# Sheet1.net
KiCad netlist of a schematic drawn in Altium Designer
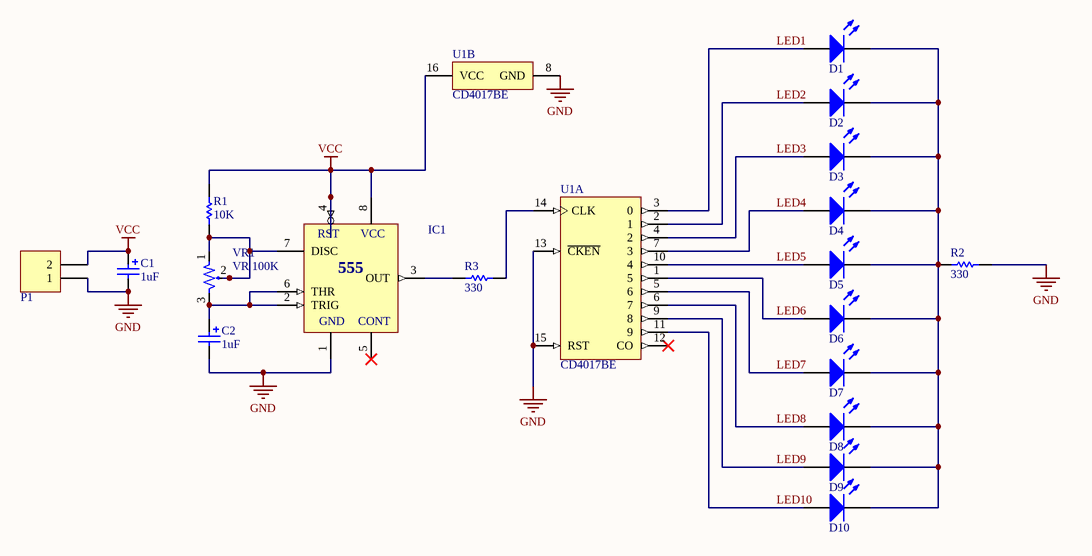
[diagram p0: Sheet1.SchDoc]

(export (version "E")
  (design (tool "Eeschema 10.0.6"))
  (components
    (comp (ref "C1")
      (value "1uF")
      (footprint "CP1/2")
      (description "Polarized Capacitor (Radial)")
      (fields (field (name "Comment") "Cap Pol"))
      (libsource (lib "PIF_Library") (part "Cap Pol"))
    )
    (comp (ref "C2")
      (value "1uF")
      (footprint "CP1/2")
      (description "Polarized Capacitor (Radial)")
      (fields (field (name "Comment") "Cap Pol"))
      (libsource (lib "PIF_Library") (part "Cap Pol"))
    )
    (comp (ref "D1") (value "LED") (footprint "LED-5mm") (libsource (lib "PIF_Library") (part "LED")))
    (comp (ref "D2") (value "LED") (footprint "LED-5mm") (libsource (lib "PIF_Library") (part "LED")))
    (comp (ref "D3") (value "LED") (footprint "LED-5mm") (libsource (lib "PIF_Library") (part "LED")))
    (comp (ref "D4") (value "LED") (footprint "LED-5mm") (libsource (lib "PIF_Library") (part "LED")))
    (comp (ref "D5") (value "LED") (footprint "LED-5mm") (libsource (lib "PIF_Library") (part "LED")))
    (comp (ref "D6") (value "LED") (footprint "LED-5mm") (libsource (lib "PIF_Library") (part "LED")))
    (comp (ref "D7") (value "LED") (footprint "LED-5mm") (libsource (lib "PIF_Library") (part "LED")))
    (comp (ref "D8") (value "LED") (footprint "LED-5mm") (libsource (lib "PIF_Library") (part "LED")))
    (comp (ref "D9") (value "LED") (footprint "LED-5mm") (libsource (lib "PIF_Library") (part "LED")))
    (comp (ref "D10") (value "LED") (footprint "LED-5mm") (libsource (lib "PIF_Library") (part "LED")))
    (comp (ref "IC1")
      (value "LM555")
      (footprint "DIP8/W0.3")
      (description "Timer")
      (libsource (lib "PIF_Library") (part "LM555"))
    )
    (comp (ref "P1")
      (value "Domino 2")
      (footprint "DOMINO 2- 5mm")
      (description "Domino, 2-Pin")
      (fields (field (name "PUBLISHER") "Altium Limited"))
      (libsource (lib "PIF_Library") (part "Domino 2"))
    )
    (comp (ref "R1")
      (value "10K")
      (footprint "RES 1/2W")
      (description "Resistor")
      (fields (field (name "Comment") "RESISTOR"))
      (libsource (lib "PIF_Library") (part "RESISTOR"))
    )
    (comp (ref "R2")
      (value "330")
      (footprint "RES 1/2W")
      (description "Resistor")
      (fields (field (name "Comment") "RESISTOR"))
      (libsource (lib "PIF_Library") (part "RESISTOR"))
    )
    (comp (ref "R3")
      (value "330")
      (footprint "RES 1/2W")
      (description "Resistor")
      (fields (field (name "Comment") "RESISTOR"))
      (libsource (lib "PIF_Library") (part "RESISTOR"))
    )
    (comp (ref "U1")
      (value "CD4017BE")
      (footprint "DIP16/W0.3")
      (description "IC 10-OUT DECADE COUNTER 16-DIP")
      (fields (field (name "MFR") "Texas Instruments"))
      (libsource (lib "PIF_Library") (part "CD4017"))
    )
    (comp (ref "VR1")
      (value "VR 100K")
      (footprint "Varistor 1")
      (description "Var Resistor")
      (fields (field (name "Comment") "10K"))
      (libsource (lib "PIF_Library") (part "Var Resistor"))
    )
  )
  (nets
    (net (code "1") (name "/LED1") (class "Default")
      (node (ref "D1") (pin "1") (pinfunction "A_1") (pintype "passive"))
      (node (ref "U1") (pin "3") (pinfunction "0_3") (pintype "output"))
    )
    (net (code "2") (name "/LED2") (class "Default")
      (node (ref "D2") (pin "1") (pinfunction "A_1") (pintype "passive"))
      (node (ref "U1") (pin "2") (pinfunction "1_2") (pintype "output"))
    )
    (net (code "3") (name "/LED3") (class "Default")
      (node (ref "D3") (pin "1") (pinfunction "A_1") (pintype "passive"))
      (node (ref "U1") (pin "4") (pinfunction "2_4") (pintype "output"))
    )
    (net (code "4") (name "/LED4") (class "Default")
      (node (ref "D4") (pin "1") (pinfunction "A_1") (pintype "passive"))
      (node (ref "U1") (pin "7") (pinfunction "3_7") (pintype "output"))
    )
    (net (code "5") (name "/LED5") (class "Default")
      (node (ref "D5") (pin "1") (pinfunction "A_1") (pintype "passive"))
      (node (ref "U1") (pin "10") (pinfunction "4_10") (pintype "output"))
    )
    (net (code "6") (name "/LED6") (class "Default")
      (node (ref "D6") (pin "1") (pinfunction "A_1") (pintype "passive"))
      (node (ref "U1") (pin "1") (pinfunction "5_1") (pintype "output"))
    )
    (net (code "7") (name "/LED7") (class "Default")
      (node (ref "D7") (pin "1") (pinfunction "A_1") (pintype "passive"))
      (node (ref "U1") (pin "5") (pinfunction "6_5") (pintype "output"))
    )
    (net (code "8") (name "/LED8") (class "Default")
      (node (ref "D8") (pin "1") (pinfunction "A_1") (pintype "passive"))
      (node (ref "U1") (pin "6") (pinfunction "7_6") (pintype "output"))
    )
    (net (code "9") (name "/LED9") (class "Default")
      (node (ref "D9") (pin "1") (pinfunction "A_1") (pintype "passive"))
      (node (ref "U1") (pin "9") (pinfunction "8_9") (pintype "output"))
    )
    (net (code "10") (name "/LED10") (class "Default")
      (node (ref "D10") (pin "1") (pinfunction "A_1") (pintype "passive"))
      (node (ref "U1") (pin "11") (pinfunction "9_11") (pintype "output"))
    )
    (net (code "11") (name "GND") (class "Default")
      (node (ref "C1") (pin "2") (pinfunction "2_2") (pintype "passive"))
      (node (ref "C2") (pin "2") (pinfunction "2_2") (pintype "passive"))
      (node (ref "IC1") (pin "1") (pinfunction "GND_1") (pintype "power_in"))
      (node (ref "P1") (pin "1") (pinfunction "1_1") (pintype "passive"))
      (node (ref "R2") (pin "1") (pinfunction "1_1") (pintype "passive"))
      (node (ref "U1") (pin "13") (pinfunction "~{CKEN}_13") (pintype "input"))
      (node (ref "U1") (pin "15") (pinfunction "RST_15") (pintype "input"))
      (node (ref "U1") (pin "8") (pinfunction "GND_8") (pintype "passive"))
    )
    (net (code "12") (name "Net-(D1-K)") (class "Default")
      (node (ref "D1") (pin "2") (pinfunction "K_2") (pintype "passive"))
      (node (ref "D10") (pin "2") (pinfunction "K_2") (pintype "passive"))
      (node (ref "D2") (pin "2") (pinfunction "K_2") (pintype "passive"))
      (node (ref "D3") (pin "2") (pinfunction "K_2") (pintype "passive"))
      (node (ref "D4") (pin "2") (pinfunction "K_2") (pintype "passive"))
      (node (ref "D5") (pin "2") (pinfunction "K_2") (pintype "passive"))
      (node (ref "D6") (pin "2") (pinfunction "K_2") (pintype "passive"))
      (node (ref "D7") (pin "2") (pinfunction "K_2") (pintype "passive"))
      (node (ref "D8") (pin "2") (pinfunction "K_2") (pintype "passive"))
      (node (ref "D9") (pin "2") (pinfunction "K_2") (pintype "passive"))
      (node (ref "R2") (pin "2") (pinfunction "2_2") (pintype "passive"))
    )
    (net (code "13") (name "Net-(IC1-DISC)") (class "Default")
      (node (ref "IC1") (pin "7") (pinfunction "DISC_7") (pintype "open_collector"))
      (node (ref "R1") (pin "1") (pinfunction "1_1") (pintype "passive"))
      (node (ref "VR1") (pin "1") (pinfunction "1_1") (pintype "passive"))
      (node (ref "VR1") (pin "2") (pinfunction "2_2") (pintype "passive"))
    )
    (net (code "14") (name "Net-(IC1-OUT)") (class "Default")
      (node (ref "IC1") (pin "3") (pinfunction "OUT_3") (pintype "output"))
      (node (ref "R3") (pin "2") (pinfunction "2_2") (pintype "passive"))
    )
    (net (code "15") (name "Net-(IC1-THR)") (class "Default")
      (node (ref "C2") (pin "1") (pinfunction "1_1") (pintype "passive"))
      (node (ref "IC1") (pin "2") (pinfunction "TRIG_2") (pintype "input"))
      (node (ref "IC1") (pin "6") (pinfunction "THR_6") (pintype "input"))
      (node (ref "VR1") (pin "3") (pinfunction "3_3") (pintype "passive"))
    )
    (net (code "16") (name "Net-(U1A-CLK)") (class "Default")
      (node (ref "R3") (pin "1") (pinfunction "1_1") (pintype "passive"))
      (node (ref "U1") (pin "14") (pinfunction "CLK_14") (pintype "input"))
    )
    (net (code "17") (name "VCC") (class "Default")
      (node (ref "C1") (pin "1") (pinfunction "1_1") (pintype "passive"))
      (node (ref "IC1") (pin "4") (pinfunction "RST_4") (pintype "input"))
      (node (ref "IC1") (pin "8") (pinfunction "VCC_8") (pintype "power_in"))
      (node (ref "P1") (pin "2") (pinfunction "2_2") (pintype "passive"))
      (node (ref "R1") (pin "2") (pinfunction "2_2") (pintype "passive"))
      (node (ref "U1") (pin "16") (pinfunction "VCC_16") (pintype "passive"))
    )
    (net (code "18") (name "unconnected-(IC1-CONT-Pad5)") (class "Default")
      (node (ref "IC1") (pin "5") (pinfunction "CONT_5") (pintype "passive+no_connect"))
    )
    (net (code "19") (name "unconnected-(U1A-CO-Pad12)") (class "Default")
      (node (ref "U1") (pin "12") (pinfunction "CO_12") (pintype "output+no_connect"))
    )
  )
)
